# rx_mod-2.net
KiCad netlist of a schematic drawn in EAGLE
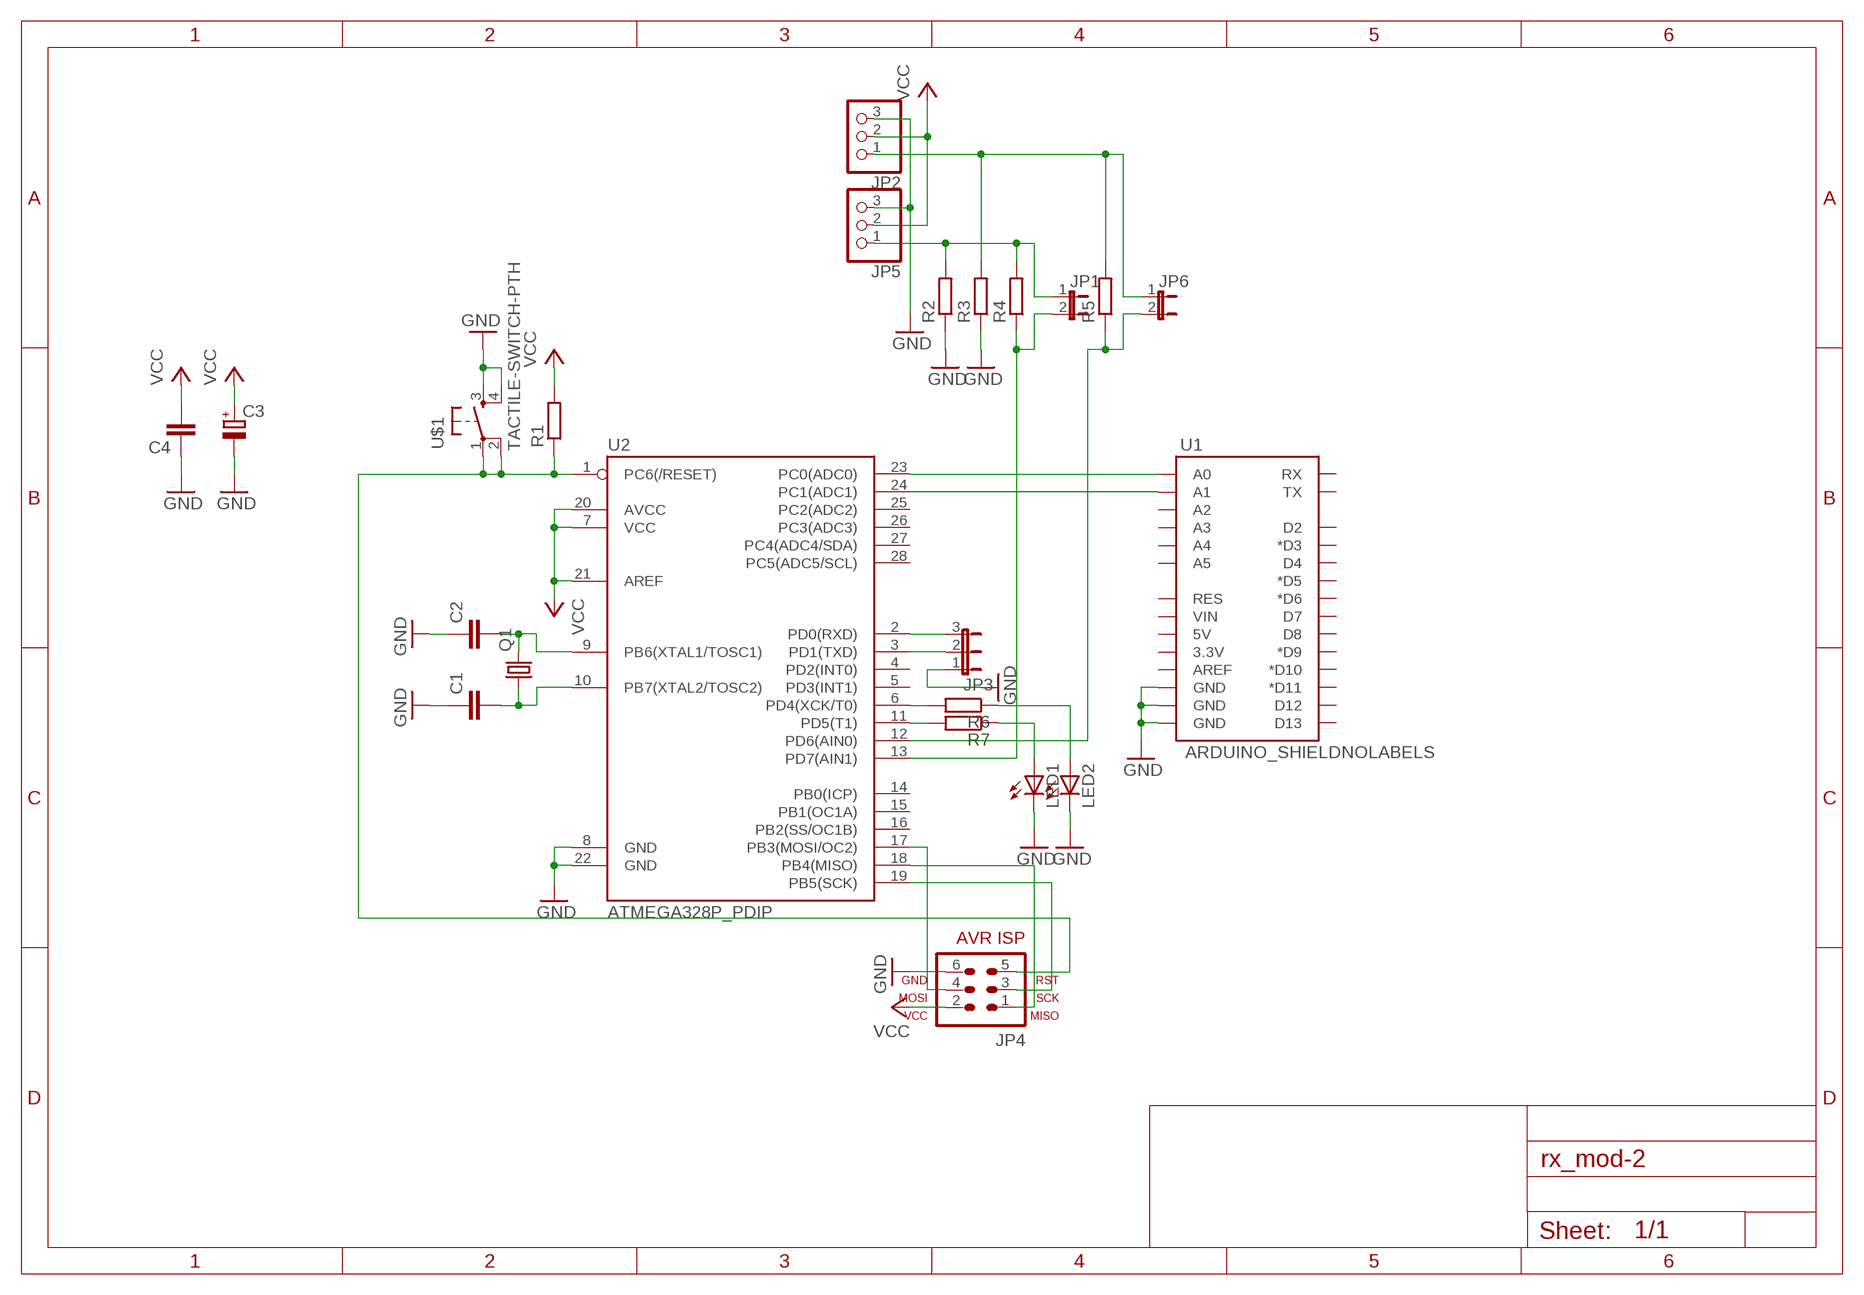
[diagram p0: schematic, sheet 1]

(export (version "E")
  (design (tool "Eeschema 10.0.6"))
  (components
    (comp (ref "C1")
      (value "C-EU050-030X075")
      (footprint "eagle-import:C050-030X075")
      (libsource (lib "eagle-import") (part "C-EU050-030X075"))
    )
    (comp (ref "C2")
      (value "C-EU050-030X075")
      (footprint "eagle-import:C050-030X075")
      (libsource (lib "eagle-import") (part "C-EU050-030X075"))
    )
    (comp (ref "C3")
      (value "CPOL-EUE2.5-6")
      (footprint "eagle-import:E2,5-6")
      (libsource (lib "eagle-import") (part "CPOL-EUE2.5-6"))
    )
    (comp (ref "C4")
      (value "C-EU050-030X075")
      (footprint "eagle-import:C050-030X075")
      (libsource (lib "eagle-import") (part "C-EU050-030X075"))
    )
    (comp (ref "JP1")
      (value "JP1E")
      (footprint "eagle-import:JP1")
      (libsource (lib "eagle-import") (part "JP1E"))
    )
    (comp (ref "JP2")
      (value "PINHD-1X3/90")
      (footprint "eagle-import:1X03_90")
      (libsource (lib "eagle-import") (part "PINHD-1X3/90"))
    )
    (comp (ref "JP3")
      (value "JP2E")
      (footprint "eagle-import:JP2")
      (libsource (lib "eagle-import") (part "JP2E"))
    )
    (comp (ref "JP4")
      (value "AVR-ISP-6VERT")
      (footprint "eagle-import:AVR-ISP-6")
      (libsource (lib "eagle-import") (part "AVR-ISP-6VERT"))
    )
    (comp (ref "JP5")
      (value "PINHD-1X3/90")
      (footprint "eagle-import:1X03_90")
      (libsource (lib "eagle-import") (part "PINHD-1X3/90"))
    )
    (comp (ref "JP6")
      (value "JP1E")
      (footprint "eagle-import:JP1")
      (libsource (lib "eagle-import") (part "JP1E"))
    )
    (comp (ref "LED1")
      (value "LED5MM")
      (footprint "eagle-import:LED5MM")
      (libsource (lib "eagle-import") (part "LED5MM"))
    )
    (comp (ref "LED2")
      (value "LED5MM")
      (footprint "eagle-import:LED5MM")
      (libsource (lib "eagle-import") (part "LED5MM"))
    )
    (comp (ref "Q1")
      (value "CRYSTALHC49U70")
      (footprint "eagle-import:HC49U70")
      (libsource (lib "eagle-import") (part "CRYSTALHC49U70"))
    )
    (comp (ref "R1")
      (value "R-EU_0207/10")
      (footprint "eagle-import:0207_10")
      (libsource (lib "eagle-import") (part "R-EU_0207/10"))
    )
    (comp (ref "R2")
      (value "R-EU_0207/10")
      (footprint "eagle-import:0207_10")
      (libsource (lib "eagle-import") (part "R-EU_0207/10"))
    )
    (comp (ref "R3")
      (value "R-EU_0207/10")
      (footprint "eagle-import:0207_10")
      (libsource (lib "eagle-import") (part "R-EU_0207/10"))
    )
    (comp (ref "R4")
      (value "R-EU_0207/10")
      (footprint "eagle-import:0207_10")
      (libsource (lib "eagle-import") (part "R-EU_0207/10"))
    )
    (comp (ref "R5")
      (value "R-EU_0207/10")
      (footprint "eagle-import:0207_10")
      (libsource (lib "eagle-import") (part "R-EU_0207/10"))
    )
    (comp (ref "R6")
      (value "R-EU_0207/10")
      (footprint "eagle-import:0207_10")
      (libsource (lib "eagle-import") (part "R-EU_0207/10"))
    )
    (comp (ref "R7")
      (value "R-EU_0207/10")
      (footprint "eagle-import:0207_10")
      (libsource (lib "eagle-import") (part "R-EU_0207/10"))
    )
    (comp (ref "U$1")
      (value "TACTILE-SWITCH-PTH")
      (footprint "eagle-import:TAC-SWITCH-PTH")
      (libsource (lib "eagle-import") (part "TACTILE-SWITCH-PTH"))
    )
    (comp (ref "U1")
      (value "ARDUINO_SHIELDNOLABELS")
      (footprint "eagle-import:DUEMILANOVE_SHIELD_NOLABELS")
      (libsource (lib "eagle-import") (part "ARDUINO_SHIELDNOLABELS"))
    )
    (comp (ref "U2")
      (value "ATMEGA328P_PDIP")
      (footprint "eagle-import:DIL28-3")
      (libsource (lib "eagle-import") (part "ATMEGA328P_PDIP"))
    )
  )
  (nets
    (net (code "1") (name "GND") (class "Default")
      (node (ref "C1") (pin "1") (pinfunction "1_1") (pintype "passive"))
      (node (ref "C2") (pin "1") (pinfunction "1_1") (pintype "passive"))
      (node (ref "C3") (pin "-") (pinfunction "-_-") (pintype "passive"))
      (node (ref "C4") (pin "1") (pinfunction "1_1") (pintype "passive"))
      (node (ref "JP2") (pin "3") (pinfunction "3_3") (pintype "passive"))
      (node (ref "JP3") (pin "1") (pinfunction "1_1") (pintype "passive"))
      (node (ref "JP4") (pin "6") (pinfunction "6_6") (pintype "passive"))
      (node (ref "JP5") (pin "3") (pinfunction "3_3") (pintype "passive"))
      (node (ref "LED1") (pin "K") (pinfunction "C_K") (pintype "passive"))
      (node (ref "LED2") (pin "K") (pinfunction "C_K") (pintype "passive"))
      (node (ref "R2") (pin "1") (pinfunction "1_1") (pintype "passive"))
      (node (ref "R3") (pin "1") (pinfunction "1_1") (pintype "passive"))
      (node (ref "U$1") (pin "3") (pinfunction "3_3") (pintype "passive"))
      (node (ref "U$1") (pin "4") (pinfunction "4_4") (pintype "passive"))
      (node (ref "U1") (pin "GND@0") (pinfunction "GND_GND@0") (pintype "bidirectional"))
      (node (ref "U1") (pin "GND@1") (pinfunction "GND_GND@1") (pintype "bidirectional"))
      (node (ref "U1") (pin "GND@2") (pinfunction "GND_GND@2") (pintype "bidirectional"))
      (node (ref "U2") (pin "22") (pinfunction "GND_22") (pintype "bidirectional"))
      (node (ref "U2") (pin "8") (pinfunction "GND_8") (pintype "bidirectional"))
    )
    (net (code "2") (name "Net-(JP1-Pad1)") (class "Default")
      (node (ref "JP1") (pin "1") (pinfunction "1_1") (pintype "passive"))
      (node (ref "JP5") (pin "1") (pinfunction "1_1") (pintype "passive"))
      (node (ref "R2") (pin "2") (pinfunction "2_2") (pintype "passive"))
      (node (ref "R4") (pin "2") (pinfunction "2_2") (pintype "passive"))
    )
    (net (code "3") (name "Net-(JP2-Pad1)") (class "Default")
      (node (ref "JP2") (pin "1") (pinfunction "1_1") (pintype "passive"))
      (node (ref "JP6") (pin "1") (pinfunction "1_1") (pintype "passive"))
      (node (ref "R3") (pin "2") (pinfunction "2_2") (pintype "passive"))
      (node (ref "R5") (pin "2") (pinfunction "2_2") (pintype "passive"))
    )
    (net (code "4") (name "Net-(LED1-PadA)") (class "Default")
      (node (ref "LED1") (pin "A") (pinfunction "A_A") (pintype "passive"))
      (node (ref "R7") (pin "1") (pinfunction "1_1") (pintype "passive"))
    )
    (net (code "5") (name "Net-(LED2-PadA)") (class "Default")
      (node (ref "LED2") (pin "A") (pinfunction "A_A") (pintype "passive"))
      (node (ref "R6") (pin "1") (pinfunction "1_1") (pintype "passive"))
    )
    (net (code "6") (name "Net-(U2-PB3(MOSI{slash}OC2))") (class "Default")
      (node (ref "JP4") (pin "4") (pinfunction "4_4") (pintype "passive"))
      (node (ref "U2") (pin "17") (pinfunction "PB3(MOSI/OC2)_17") (pintype "bidirectional"))
    )
    (net (code "7") (name "Net-(U2-PB4(MISO))") (class "Default")
      (node (ref "JP4") (pin "1") (pinfunction "1_1") (pintype "passive"))
      (node (ref "U2") (pin "18") (pinfunction "PB4(MISO)_18") (pintype "bidirectional"))
    )
    (net (code "8") (name "Net-(U2-PB5(SCK))") (class "Default")
      (node (ref "JP4") (pin "3") (pinfunction "3_3") (pintype "passive"))
      (node (ref "U2") (pin "19") (pinfunction "PB5(SCK)_19") (pintype "bidirectional"))
    )
    (net (code "9") (name "Net-(U2-PB6(XTAL1{slash}TOSC1))") (class "Default")
      (node (ref "C2") (pin "2") (pinfunction "2_2") (pintype "passive"))
      (node (ref "Q1") (pin "2") (pinfunction "2_2") (pintype "passive"))
      (node (ref "U2") (pin "9") (pinfunction "PB6(XTAL1/TOSC1)_9") (pintype "bidirectional"))
    )
    (net (code "10") (name "Net-(U2-PB7(XTAL2{slash}TOSC2))") (class "Default")
      (node (ref "C1") (pin "2") (pinfunction "2_2") (pintype "passive"))
      (node (ref "Q1") (pin "1") (pinfunction "1_1") (pintype "passive"))
      (node (ref "U2") (pin "10") (pinfunction "PB7(XTAL2/TOSC2)_10") (pintype "bidirectional"))
    )
    (net (code "11") (name "Net-(U2-PC0(ADC0))") (class "Default")
      (node (ref "U1") (pin "A0") (pinfunction "A0_A0") (pintype "bidirectional"))
      (node (ref "U2") (pin "23") (pinfunction "PC0(ADC0)_23") (pintype "bidirectional"))
    )
    (net (code "12") (name "Net-(U2-PC1(ADC1))") (class "Default")
      (node (ref "U1") (pin "A1") (pinfunction "A1_A1") (pintype "bidirectional"))
      (node (ref "U2") (pin "24") (pinfunction "PC1(ADC1)_24") (pintype "bidirectional"))
    )
    (net (code "13") (name "Net-(U2-PC6({slash}RESET))") (class "Default")
      (node (ref "JP4") (pin "5") (pinfunction "5_5") (pintype "passive"))
      (node (ref "R1") (pin "1") (pinfunction "1_1") (pintype "passive"))
      (node (ref "U$1") (pin "1") (pinfunction "1_1") (pintype "passive"))
      (node (ref "U$1") (pin "2") (pinfunction "2_2") (pintype "passive"))
      (node (ref "U2") (pin "1") (pinfunction "PC6(/RESET)_1") (pintype "bidirectional"))
    )
    (net (code "14") (name "Net-(U2-PD0(RXD))") (class "Default")
      (node (ref "JP3") (pin "3") (pinfunction "3_3") (pintype "passive"))
      (node (ref "U2") (pin "2") (pinfunction "PD0(RXD)_2") (pintype "bidirectional"))
    )
    (net (code "15") (name "Net-(U2-PD1(TXD))") (class "Default")
      (node (ref "JP3") (pin "2") (pinfunction "2_2") (pintype "passive"))
      (node (ref "U2") (pin "3") (pinfunction "PD1(TXD)_3") (pintype "bidirectional"))
    )
    (net (code "16") (name "Net-(U2-PD4(XCK{slash}T0))") (class "Default")
      (node (ref "R6") (pin "2") (pinfunction "2_2") (pintype "passive"))
      (node (ref "U2") (pin "6") (pinfunction "PD4(XCK/T0)_6") (pintype "bidirectional"))
    )
    (net (code "17") (name "Net-(U2-PD5(T1))") (class "Default")
      (node (ref "R7") (pin "2") (pinfunction "2_2") (pintype "passive"))
      (node (ref "U2") (pin "11") (pinfunction "PD5(T1)_11") (pintype "bidirectional"))
    )
    (net (code "18") (name "Net-(U2-PD6(AIN0))") (class "Default")
      (node (ref "JP6") (pin "2") (pinfunction "2_2") (pintype "passive"))
      (node (ref "R5") (pin "1") (pinfunction "1_1") (pintype "passive"))
      (node (ref "U2") (pin "12") (pinfunction "PD6(AIN0)_12") (pintype "bidirectional"))
    )
    (net (code "19") (name "Net-(U2-PD7(AIN1))") (class "Default")
      (node (ref "JP1") (pin "2") (pinfunction "2_2") (pintype "passive"))
      (node (ref "R4") (pin "1") (pinfunction "1_1") (pintype "passive"))
      (node (ref "U2") (pin "13") (pinfunction "PD7(AIN1)_13") (pintype "bidirectional"))
    )
    (net (code "20") (name "VCC") (class "Default")
      (node (ref "C3") (pin "+") (pinfunction "+_+") (pintype "passive"))
      (node (ref "C4") (pin "2") (pinfunction "2_2") (pintype "passive"))
      (node (ref "JP2") (pin "2") (pinfunction "2_2") (pintype "passive"))
      (node (ref "JP4") (pin "2") (pinfunction "2_2") (pintype "passive"))
      (node (ref "JP5") (pin "2") (pinfunction "2_2") (pintype "passive"))
      (node (ref "R1") (pin "2") (pinfunction "2_2") (pintype "passive"))
      (node (ref "U2") (pin "20") (pinfunction "AVCC_20") (pintype "bidirectional"))
      (node (ref "U2") (pin "21") (pinfunction "AREF_21") (pintype "bidirectional"))
      (node (ref "U2") (pin "7") (pinfunction "VCC_7") (pintype "bidirectional"))
    )
    (net (code "21") (name "unconnected-(U1-*D3-PadD3)") (class "Default")
      (node (ref "U1") (pin "D3") (pinfunction "*D3_D3") (pintype "bidirectional"))
    )
    (net (code "22") (name "unconnected-(U1-*D5-PadD5)") (class "Default")
      (node (ref "U1") (pin "D5") (pinfunction "*D5_D5") (pintype "bidirectional"))
    )
    (net (code "23") (name "unconnected-(U1-*D6-PadD6)") (class "Default")
      (node (ref "U1") (pin "D6") (pinfunction "*D6_D6") (pintype "bidirectional"))
    )
    (net (code "24") (name "unconnected-(U1-*D9-PadD9)") (class "Default")
      (node (ref "U1") (pin "D9") (pinfunction "*D9_D9") (pintype "bidirectional"))
    )
    (net (code "25") (name "unconnected-(U1-*D10-PadD10)") (class "Default")
      (node (ref "U1") (pin "D10") (pinfunction "*D10_D10") (pintype "bidirectional"))
    )
    (net (code "26") (name "unconnected-(U1-*D11-PadD11)") (class "Default")
      (node (ref "U1") (pin "D11") (pinfunction "*D11_D11") (pintype "bidirectional"))
    )
    (net (code "27") (name "unconnected-(U1-Pad3.3V)") (class "Default")
      (node (ref "U1") (pin "3.3V") (pinfunction "3.3V_3.3V") (pintype "bidirectional"))
    )
    (net (code "28") (name "unconnected-(U1-Pad5V)") (class "Default")
      (node (ref "U1") (pin "5V") (pinfunction "5V_5V") (pintype "bidirectional"))
    )
    (net (code "29") (name "unconnected-(U1-PadA2)") (class "Default")
      (node (ref "U1") (pin "A2") (pinfunction "A2_A2") (pintype "bidirectional"))
    )
    (net (code "30") (name "unconnected-(U1-PadA3)") (class "Default")
      (node (ref "U1") (pin "A3") (pinfunction "A3_A3") (pintype "bidirectional"))
    )
    (net (code "31") (name "unconnected-(U1-PadA4)") (class "Default")
      (node (ref "U1") (pin "A4") (pinfunction "A4_A4") (pintype "bidirectional"))
    )
    (net (code "32") (name "unconnected-(U1-PadA5)") (class "Default")
      (node (ref "U1") (pin "A5") (pinfunction "A5_A5") (pintype "bidirectional"))
    )
    (net (code "33") (name "unconnected-(U1-PadAREF)") (class "Default")
      (node (ref "U1") (pin "AREF") (pinfunction "AREF_AREF") (pintype "bidirectional"))
    )
    (net (code "34") (name "unconnected-(U1-PadD2)") (class "Default")
      (node (ref "U1") (pin "D2") (pinfunction "D2_D2") (pintype "bidirectional"))
    )
    (net (code "35") (name "unconnected-(U1-PadD4)") (class "Default")
      (node (ref "U1") (pin "D4") (pinfunction "D4_D4") (pintype "bidirectional"))
    )
    (net (code "36") (name "unconnected-(U1-PadD7)") (class "Default")
      (node (ref "U1") (pin "D7") (pinfunction "D7_D7") (pintype "bidirectional"))
    )
    (net (code "37") (name "unconnected-(U1-PadD8)") (class "Default")
      (node (ref "U1") (pin "D8") (pinfunction "D8_D8") (pintype "bidirectional"))
    )
    (net (code "38") (name "unconnected-(U1-PadD12)") (class "Default")
      (node (ref "U1") (pin "D12") (pinfunction "D12_D12") (pintype "bidirectional"))
    )
    (net (code "39") (name "unconnected-(U1-PadD13)") (class "Default")
      (node (ref "U1") (pin "D13") (pinfunction "D13_D13") (pintype "bidirectional"))
    )
    (net (code "40") (name "unconnected-(U1-PadRES)") (class "Default")
      (node (ref "U1") (pin "RES") (pinfunction "RES_RES") (pintype "bidirectional"))
    )
    (net (code "41") (name "unconnected-(U1-PadRX)") (class "Default")
      (node (ref "U1") (pin "RX") (pinfunction "RX_RX") (pintype "bidirectional"))
    )
    (net (code "42") (name "unconnected-(U1-PadTX)") (class "Default")
      (node (ref "U1") (pin "TX") (pinfunction "TX_TX") (pintype "bidirectional"))
    )
    (net (code "43") (name "unconnected-(U1-PadVIN)") (class "Default")
      (node (ref "U1") (pin "VIN") (pinfunction "VIN_VIN") (pintype "bidirectional"))
    )
    (net (code "44") (name "unconnected-(U2-PB0(ICP)-Pad14)") (class "Default")
      (node (ref "U2") (pin "14") (pinfunction "PB0(ICP)_14") (pintype "bidirectional"))
    )
    (net (code "45") (name "unconnected-(U2-PB1(OC1A)-Pad15)") (class "Default")
      (node (ref "U2") (pin "15") (pinfunction "PB1(OC1A)_15") (pintype "bidirectional"))
    )
    (net (code "46") (name "unconnected-(U2-PB2(SS{slash}OC1B)-Pad16)") (class "Default")
      (node (ref "U2") (pin "16") (pinfunction "PB2(SS/OC1B)_16") (pintype "bidirectional"))
    )
    (net (code "47") (name "unconnected-(U2-PC2(ADC2)-Pad25)") (class "Default")
      (node (ref "U2") (pin "25") (pinfunction "PC2(ADC2)_25") (pintype "bidirectional"))
    )
    (net (code "48") (name "unconnected-(U2-PC3(ADC3)-Pad26)") (class "Default")
      (node (ref "U2") (pin "26") (pinfunction "PC3(ADC3)_26") (pintype "bidirectional"))
    )
    (net (code "49") (name "unconnected-(U2-PC4(ADC4{slash}SDA)-Pad27)") (class "Default")
      (node (ref "U2") (pin "27") (pinfunction "PC4(ADC4/SDA)_27") (pintype "bidirectional"))
    )
    (net (code "50") (name "unconnected-(U2-PC5(ADC5{slash}SCL)-Pad28)") (class "Default")
      (node (ref "U2") (pin "28") (pinfunction "PC5(ADC5/SCL)_28") (pintype "bidirectional"))
    )
    (net (code "51") (name "unconnected-(U2-PD2(INT0)-Pad4)") (class "Default")
      (node (ref "U2") (pin "4") (pinfunction "PD2(INT0)_4") (pintype "bidirectional"))
    )
    (net (code "52") (name "unconnected-(U2-PD3(INT1)-Pad5)") (class "Default")
      (node (ref "U2") (pin "5") (pinfunction "PD3(INT1)_5") (pintype "bidirectional"))
    )
  )
)
